# 5_-_Power.net
KiCad netlist of a schematic drawn in Altium Designer
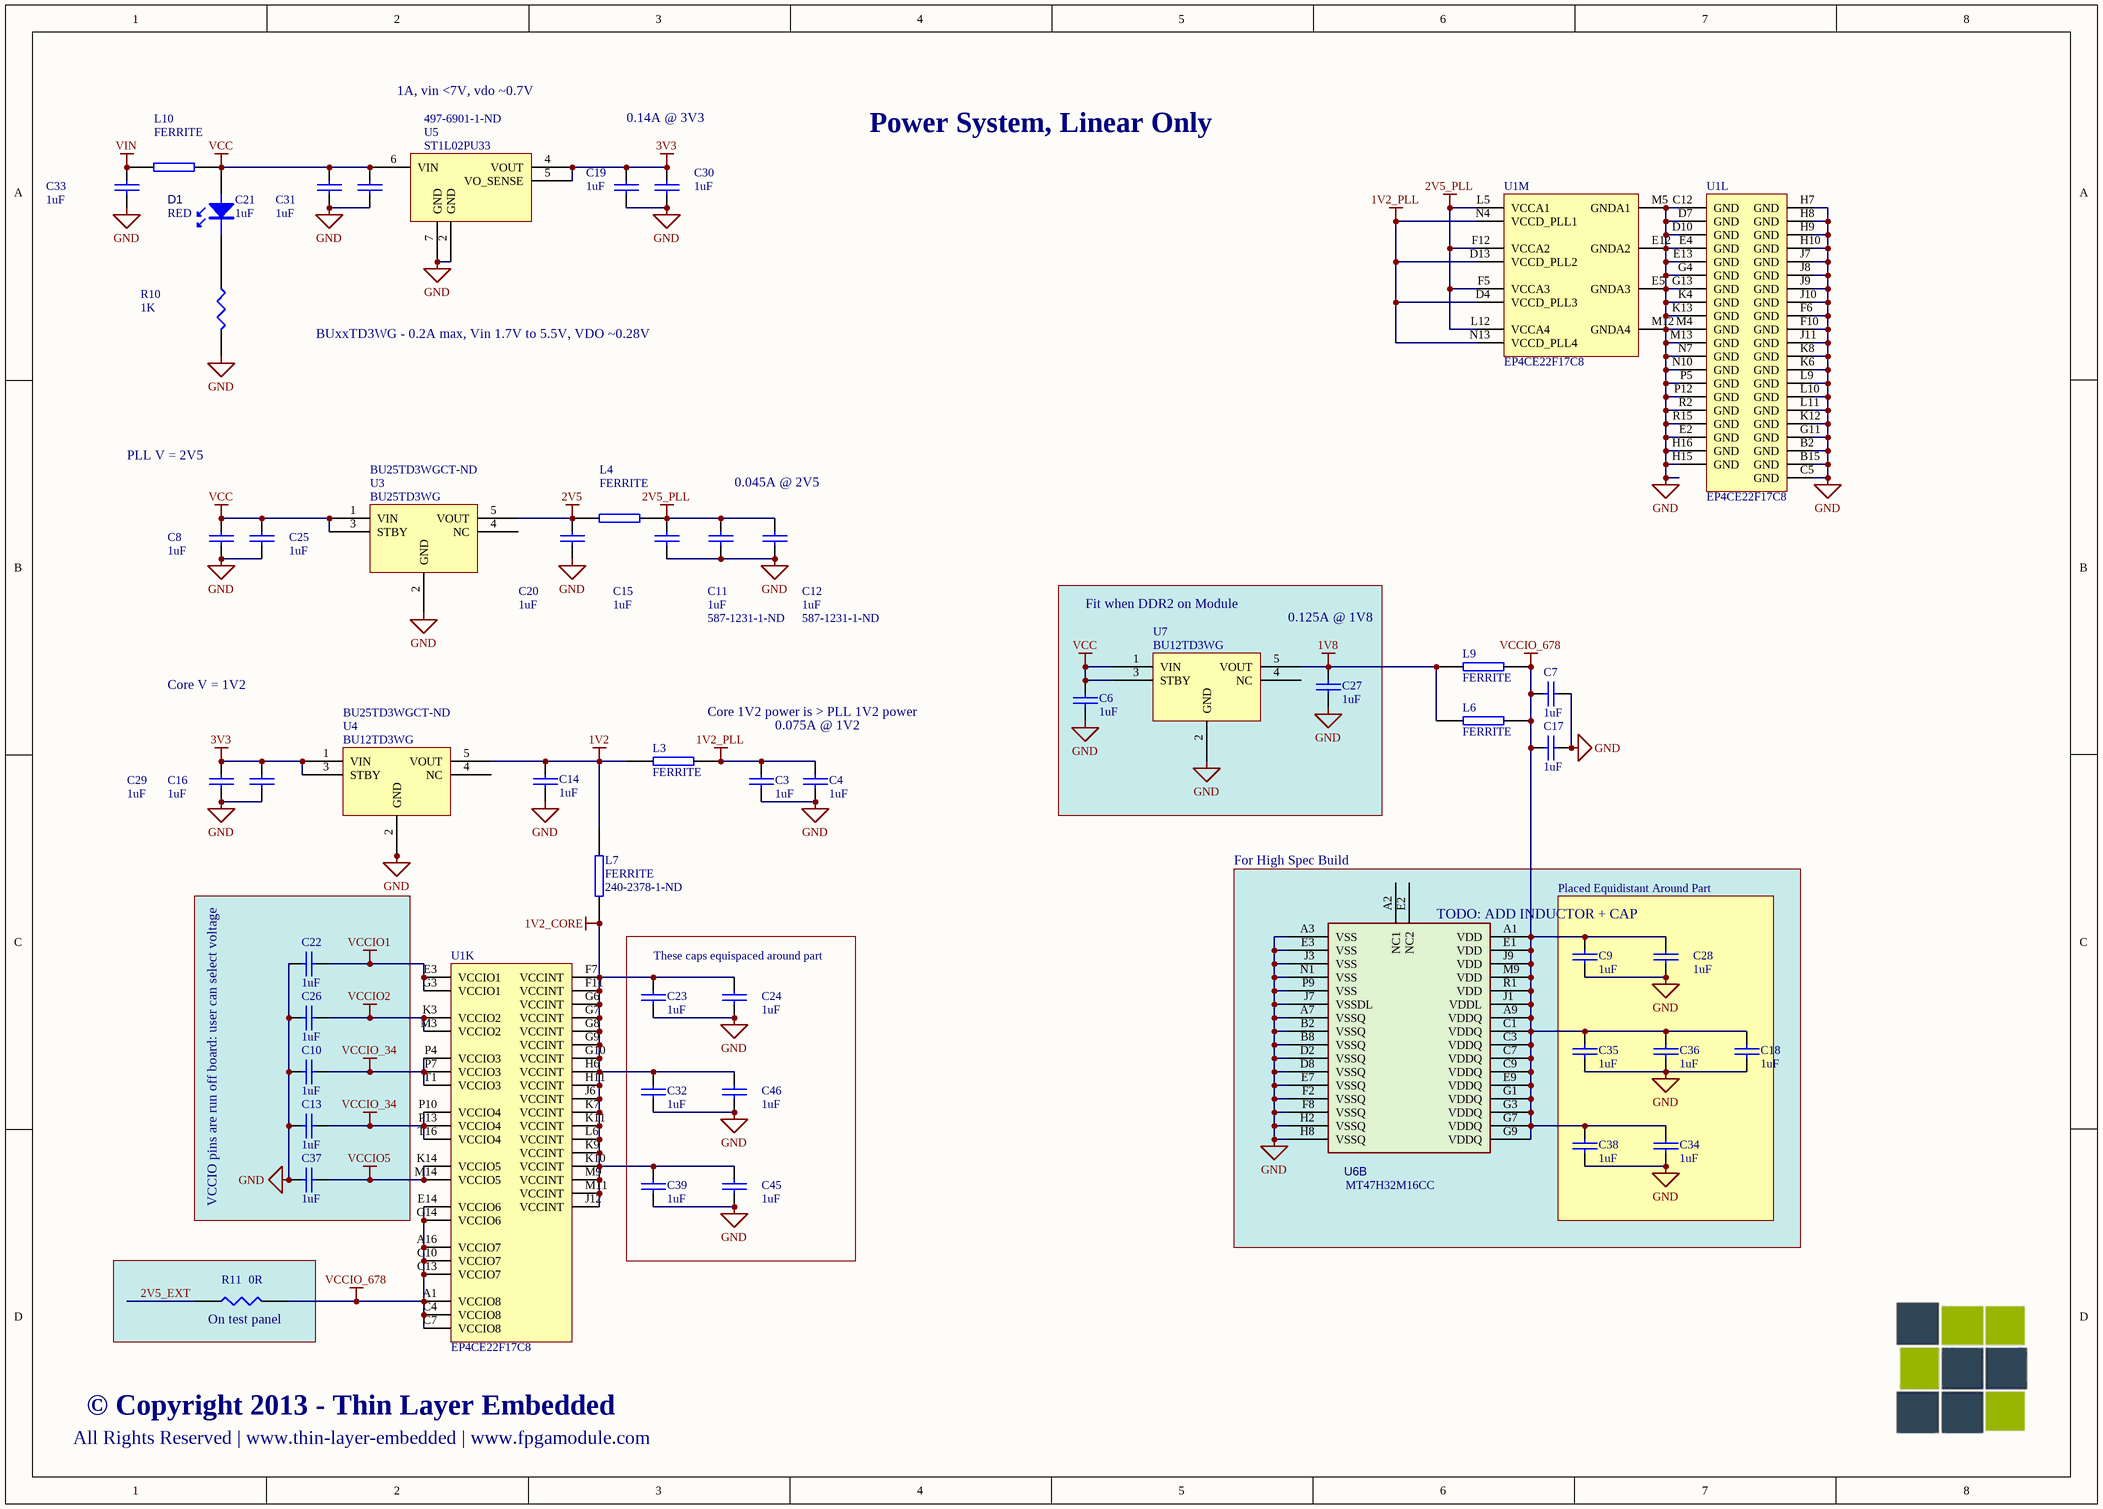
[diagram p0: 5 - Power.SchDoc]

(export (version "E")
  (design (tool "Eeschema 10.0.6"))
  (components
    (comp (ref "C3")
      (value "1uF")
      (footprint "0402_HD")
      (description "Capacitor")
      (libsource (lib "*") (part "CAP"))
    )
    (comp (ref "C4")
      (value "1uF")
      (footprint "0402_HD")
      (description "Capacitor")
      (libsource (lib "*") (part "CAP"))
    )
    (comp (ref "C6")
      (value "1uF")
      (footprint "0402_HD")
      (description "Capacitor")
      (libsource (lib "*") (part "CAP"))
    )
    (comp (ref "C7")
      (value "1uF")
      (footprint "0402_HD")
      (description "Capacitor")
      (libsource (lib "*") (part "CAP"))
    )
    (comp (ref "C8")
      (value "1uF")
      (footprint "0402_HD")
      (description "Capacitor")
      (libsource (lib "*") (part "CAP"))
    )
    (comp (ref "C9")
      (value "1uF")
      (footprint "0402_HD")
      (description "Capacitor")
      (libsource (lib "*") (part "CAP"))
    )
    (comp (ref "C10")
      (value "1uF")
      (footprint "0402_HD")
      (description "Capacitor")
      (libsource (lib "*") (part "CAP"))
    )
    (comp (ref "C11")
      (value "1uF")
      (footprint "0402_HD")
      (description "Capacitor")
      (fields (field (name "SUPPLIER PART NUMBER 2") "587-1231-1-ND"))
      (libsource (lib "*") (part "CAP"))
    )
    (comp (ref "C12")
      (value "1uF")
      (footprint "0402_HD")
      (description "Capacitor")
      (fields (field (name "SUPPLIER PART NUMBER 2") "587-1231-1-ND"))
      (libsource (lib "*") (part "CAP"))
    )
    (comp (ref "C13")
      (value "1uF")
      (footprint "0402_HD")
      (description "Capacitor")
      (libsource (lib "*") (part "CAP"))
    )
    (comp (ref "C14")
      (value "1uF")
      (footprint "0402_HD")
      (description "Capacitor")
      (libsource (lib "*") (part "CAP"))
    )
    (comp (ref "C15")
      (value "1uF")
      (footprint "0402_HD")
      (description "Capacitor")
      (libsource (lib "*") (part "CAP"))
    )
    (comp (ref "C16")
      (value "1uF")
      (footprint "0402_HD")
      (description "Capacitor")
      (libsource (lib "*") (part "CAP"))
    )
    (comp (ref "C17")
      (value "1uF")
      (footprint "0402_HD")
      (description "Capacitor")
      (libsource (lib "*") (part "CAP"))
    )
    (comp (ref "C18")
      (value "1uF")
      (footprint "0402_HD")
      (description "Capacitor")
      (libsource (lib "*") (part "CAP"))
    )
    (comp (ref "C19")
      (value "1uF")
      (footprint "0402_HD")
      (description "Capacitor")
      (libsource (lib "*") (part "CAP"))
    )
    (comp (ref "C20")
      (value "1uF")
      (footprint "0402_HD")
      (description "Capacitor")
      (libsource (lib "") (part "CAP_1"))
    )
    (comp (ref "C21")
      (value "1uF")
      (footprint "0402_HD")
      (description "Capacitor")
      (libsource (lib "*") (part "CAP"))
    )
    (comp (ref "C22")
      (value "1uF")
      (footprint "0402_HD")
      (description "Capacitor")
      (libsource (lib "*") (part "CAP"))
    )
    (comp (ref "C23")
      (value "1uF")
      (footprint "0402_HD")
      (description "Capacitor")
      (libsource (lib "*") (part "CAP"))
    )
    (comp (ref "C24")
      (value "1uF")
      (footprint "0402_HD")
      (description "Capacitor")
      (libsource (lib "*") (part "CAP"))
    )
    (comp (ref "C25")
      (value "1uF")
      (footprint "0402_HD")
      (description "Capacitor")
      (libsource (lib "*") (part "CAP"))
    )
    (comp (ref "C26")
      (value "1uF")
      (footprint "0402_HD")
      (description "Capacitor")
      (libsource (lib "*") (part "CAP"))
    )
    (comp (ref "C27")
      (value "1uF")
      (footprint "0402_HD")
      (description "Capacitor")
      (libsource (lib "*") (part "CAP"))
    )
    (comp (ref "C28")
      (value "1uF")
      (footprint "0402_HD")
      (description "Capacitor")
      (libsource (lib "*") (part "CAP"))
    )
    (comp (ref "C29")
      (value "1uF")
      (footprint "0402_HD")
      (description "Capacitor")
      (libsource (lib "*") (part "CAP"))
    )
    (comp (ref "C30")
      (value "1uF")
      (footprint "0402_HD")
      (description "Capacitor")
      (libsource (lib "*") (part "CAP"))
    )
    (comp (ref "C31")
      (value "1uF")
      (footprint "0402_HD")
      (description "Capacitor")
      (libsource (lib "*") (part "CAP"))
    )
    (comp (ref "C32")
      (value "1uF")
      (footprint "0402_HD")
      (description "Capacitor")
      (libsource (lib "*") (part "CAP"))
    )
    (comp (ref "C33")
      (value "1uF")
      (footprint "0402_HD")
      (description "Capacitor")
      (libsource (lib "*") (part "CAP"))
    )
    (comp (ref "C34")
      (value "1uF")
      (footprint "0402_HD")
      (description "Capacitor")
      (libsource (lib "*") (part "CAP"))
    )
    (comp (ref "C35")
      (value "1uF")
      (footprint "0402_HD")
      (description "Capacitor")
      (libsource (lib "*") (part "CAP"))
    )
    (comp (ref "C36")
      (value "1uF")
      (footprint "0402_HD")
      (description "Capacitor")
      (libsource (lib "*") (part "CAP"))
    )
    (comp (ref "C37")
      (value "1uF")
      (footprint "0402_HD")
      (description "Capacitor")
      (libsource (lib "*") (part "CAP"))
    )
    (comp (ref "C38")
      (value "1uF")
      (footprint "0402_HD")
      (description "Capacitor")
      (libsource (lib "*") (part "CAP"))
    )
    (comp (ref "C39")
      (value "1uF")
      (footprint "0402_HD")
      (description "Capacitor")
      (libsource (lib "*") (part "CAP"))
    )
    (comp (ref "C45")
      (value "1uF")
      (footprint "0402_HD")
      (description "Capacitor")
      (libsource (lib "*") (part "CAP"))
    )
    (comp (ref "C46")
      (value "1uF")
      (footprint "0402_HD")
      (description "Capacitor")
      (libsource (lib "*") (part "CAP"))
    )
    (comp (ref "D1") (value "RED") (footprint "0402LED_HD") (libsource (lib "*") (part "LED")))
    (comp (ref "L3") (value "FERRITE") (footprint "0402_HD") (libsource (lib "*") (part "FERRITE")))
    (comp (ref "L4") (value "FERRITE") (footprint "0402_HD") (libsource (lib "*") (part "FERRITE")))
    (comp (ref "L6") (value "FERRITE") (footprint "0402_HD") (libsource (lib "*") (part "FERRITE")))
    (comp (ref "L7")
      (value "FERRITE")
      (footprint "0402_HD")
      (description "FERRITE 200MA 1000 OHM 0603 SMD")
      (fields
        (field (name "SUPPLIER PART NUMBER 1") "240-2378-1-ND")
        (field (name "MANUFACTURER") "Laird-Signal Integrity Products")
        (field (name "MANUFACTURER PART NUMBER") "HZ0603B102R-10")
      )
      (libsource (lib "*") (part "FERRITE"))
    )
    (comp (ref "L9") (value "FERRITE") (footprint "0402_HD") (libsource (lib "*") (part "FERRITE")))
    (comp (ref "L10") (value "FERRITE") (footprint "0805") (libsource (lib "*") (part "FERRITE")))
    (comp (ref "R10") (value "1K") (footprint "0402_HD") (libsource (lib "*") (part "RES1")))
    (comp (ref "R11")
      (value "0R")
      (footprint "0402_HD")
      (description "RES 24.9 OHM 1/16W 1% 0402 SMD")
      (fields
        (field (name "MANUFACTURER") "Yageo")
        (field (name "MANUFACTURER PART NUMBER") "RC0402FR-0724R9L")
      )
      (libsource (lib "*") (part "RES1"))
    )
    (comp (ref "U1")
      (value "EP4CE22F17C8")
      (footprint "FBGA256")
      (fields (field (name "PUBLISHER") "Altium Limited"))
      (libsource (lib "Altera Cyclone IV E") (part "EP4CE22F17C8"))
    )
    (comp (ref "U3")
      (value "BU25TD3WG")
      (footprint "SSOP5")
      (description "IC REG LDO 2.5V 0.2A 5SSOP")
      (fields
        (field (name "SUPPLIER PART NUMBER 1") "BU25TD3WGCT-ND")
        (field (name "MANUFACTURER") "Rohm Semiconductor")
        (field (name "MANUFACTURER PART NUMBER") "BU25TD3WG-TR")
      )
      (libsource (lib "OB_EP4CE15E22") (part "BU12TD3WG"))
    )
    (comp (ref "U4")
      (value "BU12TD3WG")
      (footprint "SSOP5")
      (description "IC REG LDO 2.5V 0.2A 5SSOP")
      (fields
        (field (name "SUPPLIER PART NUMBER 1") "BU25TD3WGCT-ND")
        (field (name "MANUFACTURER") "Rohm Semiconductor")
        (field (name "MANUFACTURER PART NUMBER") "BU25TD3WG-TR")
      )
      (libsource (lib "OB_EP4CE15E22") (part "BU12TD3WG"))
    )
    (comp (ref "U5")
      (value "ST1L02PU33")
      (footprint "DFN6")
      (description "IC VREG LDO 1A 3.3V DFN-6D")
      (fields
        (field (name "SUPPLIER PART NUMBER 1") "497-6901-1-ND")
        (field (name "MANUFACTURER") "STMicroelectronics")
        (field (name "MANUFACTURER PART NUMBER") "ST1L02PU33R")
      )
      (libsource (lib "OB_EP4CE15E22") (part "ST1L02PU33"))
    )
    (comp (ref "U6")
      (value "MT47H32M16CC")
      (footprint "DDR2_84_SPEC_HD")
      (description "IC DDR2 SDRAM 32M X 16 4 BANKS 333MHZ CAS LATENCY 5 FBGA PACKAGE 84 PINS 1.8V CORE 1.8V IO")
      (fields
        (field (name "MANUFACTURER PART NUM") "MT47H32M16CC-3:B")
        (field (name "MANUFACTURER") "Micron")
      )
      (libsource (lib "tea133-sch-2") (part "MT47H32M16CC"))
    )
    (comp (ref "U7")
      (value "BU12TD3WG")
      (footprint "SSOP5")
      (libsource (lib "OB_EP4CE15E22") (part "BU12TD3WG"))
    )
  )
  (nets
    (net (code "1") (name "/2V5_EXT") (class "Default")
      (node (ref "R11") (pin "2") (pinfunction "2_2") (pintype "passive"))
    )
    (net (code "2") (name "1V2") (class "Default")
      (node (ref "C14") (pin "1") (pinfunction "1_1") (pintype "passive"))
      (node (ref "L3") (pin "2") (pinfunction "2_2") (pintype "passive"))
      (node (ref "L7") (pin "1") (pinfunction "1_1") (pintype "passive"))
      (node (ref "U4") (pin "5") (pinfunction "VOUT_5") (pintype "passive"))
    )
    (net (code "3") (name "1V2_CORE") (class "Default")
      (node (ref "C23") (pin "1") (pinfunction "1_1") (pintype "passive"))
      (node (ref "C24") (pin "1") (pinfunction "1_1") (pintype "passive"))
      (node (ref "C32") (pin "1") (pinfunction "1_1") (pintype "passive"))
      (node (ref "C39") (pin "1") (pinfunction "1_1") (pintype "passive"))
      (node (ref "C45") (pin "1") (pinfunction "1_1") (pintype "passive"))
      (node (ref "C46") (pin "1") (pinfunction "1_1") (pintype "passive"))
      (node (ref "L7") (pin "2") (pinfunction "2_2") (pintype "passive"))
      (node (ref "U1") (pin "F11") (pinfunction "VCCINT_F11") (pintype "power_in"))
      (node (ref "U1") (pin "F7") (pinfunction "VCCINT_F7") (pintype "power_in"))
      (node (ref "U1") (pin "G10") (pinfunction "VCCINT_G10") (pintype "power_in"))
      (node (ref "U1") (pin "G6") (pinfunction "VCCINT_G6") (pintype "power_in"))
      (node (ref "U1") (pin "G7") (pinfunction "VCCINT_G7") (pintype "power_in"))
      (node (ref "U1") (pin "G8") (pinfunction "VCCINT_G8") (pintype "power_in"))
      (node (ref "U1") (pin "G9") (pinfunction "VCCINT_G9") (pintype "power_in"))
      (node (ref "U1") (pin "H11") (pinfunction "VCCINT_H11") (pintype "power_in"))
      (node (ref "U1") (pin "H6") (pinfunction "VCCINT_H6") (pintype "power_in"))
      (node (ref "U1") (pin "J12") (pinfunction "VCCINT_J12") (pintype "power_in"))
      (node (ref "U1") (pin "J6") (pinfunction "VCCINT_J6") (pintype "power_in"))
      (node (ref "U1") (pin "K10") (pinfunction "VCCINT_K10") (pintype "power_in"))
      (node (ref "U1") (pin "K11") (pinfunction "VCCINT_K11") (pintype "power_in"))
      (node (ref "U1") (pin "K7") (pinfunction "VCCINT_K7") (pintype "power_in"))
      (node (ref "U1") (pin "K9") (pinfunction "VCCINT_K9") (pintype "power_in"))
      (node (ref "U1") (pin "L6") (pinfunction "VCCINT_L6") (pintype "power_in"))
      (node (ref "U1") (pin "M11") (pinfunction "VCCINT_M11") (pintype "power_in"))
      (node (ref "U1") (pin "M9") (pinfunction "VCCINT_M9") (pintype "power_in"))
    )
    (net (code "4") (name "1V2_PLL") (class "Default")
      (node (ref "C3") (pin "1") (pinfunction "1_1") (pintype "passive"))
      (node (ref "C4") (pin "1") (pinfunction "1_1") (pintype "passive"))
      (node (ref "L3") (pin "1") (pinfunction "1_1") (pintype "passive"))
      (node (ref "U1") (pin "D13") (pinfunction "VCCD_PLL2_D13") (pintype "power_in"))
      (node (ref "U1") (pin "D4") (pinfunction "VCCD_PLL3_D4") (pintype "power_in"))
      (node (ref "U1") (pin "N13") (pinfunction "VCCD_PLL4_N13") (pintype "power_in"))
      (node (ref "U1") (pin "N4") (pinfunction "VCCD_PLL1_N4") (pintype "power_in"))
    )
    (net (code "5") (name "1V8") (class "Default")
      (node (ref "C27") (pin "1") (pinfunction "1_1") (pintype "passive"))
      (node (ref "L6") (pin "1") (pinfunction "1_1") (pintype "passive"))
      (node (ref "L9") (pin "1") (pinfunction "1_1") (pintype "passive"))
      (node (ref "U7") (pin "5") (pinfunction "VOUT_5") (pintype "passive"))
    )
    (net (code "6") (name "2V5") (class "Default")
      (node (ref "C20") (pin "2") (pinfunction "2_2") (pintype "passive"))
      (node (ref "L4") (pin "1") (pinfunction "1_1") (pintype "passive"))
      (node (ref "U3") (pin "5") (pinfunction "VOUT_5") (pintype "passive"))
    )
    (net (code "7") (name "2V5_PLL") (class "Default")
      (node (ref "C11") (pin "1") (pinfunction "1_1") (pintype "passive"))
      (node (ref "C12") (pin "1") (pinfunction "1_1") (pintype "passive"))
      (node (ref "C15") (pin "1") (pinfunction "1_1") (pintype "passive"))
      (node (ref "L4") (pin "2") (pinfunction "2_2") (pintype "passive"))
      (node (ref "U1") (pin "F12") (pinfunction "VCCA2_F12") (pintype "power_in"))
      (node (ref "U1") (pin "F5") (pinfunction "VCCA3_F5") (pintype "power_in"))
      (node (ref "U1") (pin "L12") (pinfunction "VCCA4_L12") (pintype "power_in"))
      (node (ref "U1") (pin "L5") (pinfunction "VCCA1_L5") (pintype "power_in"))
    )
    (net (code "8") (name "3V3") (class "Default")
      (node (ref "C16") (pin "1") (pinfunction "1_1") (pintype "passive"))
      (node (ref "C19") (pin "1") (pinfunction "1_1") (pintype "passive"))
      (node (ref "C29") (pin "1") (pinfunction "1_1") (pintype "passive"))
      (node (ref "C30") (pin "1") (pinfunction "1_1") (pintype "passive"))
      (node (ref "U4") (pin "1") (pinfunction "VIN_1") (pintype "passive"))
      (node (ref "U4") (pin "3") (pinfunction "STBY_3") (pintype "passive"))
      (node (ref "U5") (pin "4") (pinfunction "VOUT_4") (pintype "passive"))
      (node (ref "U5") (pin "5") (pinfunction "VO_SENSE_5") (pintype "passive"))
    )
    (net (code "9") (name "GND") (class "Default")
      (node (ref "C10") (pin "1") (pinfunction "1_1") (pintype "passive"))
      (node (ref "C11") (pin "2") (pinfunction "2_2") (pintype "passive"))
      (node (ref "C12") (pin "2") (pinfunction "2_2") (pintype "passive"))
      (node (ref "C13") (pin "1") (pinfunction "1_1") (pintype "passive"))
      (node (ref "C14") (pin "2") (pinfunction "2_2") (pintype "passive"))
      (node (ref "C15") (pin "2") (pinfunction "2_2") (pintype "passive"))
      (node (ref "C16") (pin "2") (pinfunction "2_2") (pintype "passive"))
      (node (ref "C17") (pin "2") (pinfunction "2_2") (pintype "passive"))
      (node (ref "C18") (pin "2") (pinfunction "2_2") (pintype "passive"))
      (node (ref "C19") (pin "2") (pinfunction "2_2") (pintype "passive"))
      (node (ref "C20") (pin "1") (pinfunction "1_1") (pintype "passive"))
      (node (ref "C21") (pin "2") (pinfunction "2_2") (pintype "passive"))
      (node (ref "C22") (pin "1") (pinfunction "1_1") (pintype "passive"))
      (node (ref "C23") (pin "2") (pinfunction "2_2") (pintype "passive"))
      (node (ref "C24") (pin "2") (pinfunction "2_2") (pintype "passive"))
      (node (ref "C25") (pin "2") (pinfunction "2_2") (pintype "passive"))
      (node (ref "C26") (pin "1") (pinfunction "1_1") (pintype "passive"))
      (node (ref "C27") (pin "2") (pinfunction "2_2") (pintype "passive"))
      (node (ref "C28") (pin "2") (pinfunction "2_2") (pintype "passive"))
      (node (ref "C29") (pin "2") (pinfunction "2_2") (pintype "passive"))
      (node (ref "C3") (pin "2") (pinfunction "2_2") (pintype "passive"))
      (node (ref "C30") (pin "2") (pinfunction "2_2") (pintype "passive"))
      (node (ref "C31") (pin "2") (pinfunction "2_2") (pintype "passive"))
      (node (ref "C32") (pin "2") (pinfunction "2_2") (pintype "passive"))
      (node (ref "C33") (pin "1") (pinfunction "1_1") (pintype "passive"))
      (node (ref "C34") (pin "2") (pinfunction "2_2") (pintype "passive"))
      (node (ref "C35") (pin "2") (pinfunction "2_2") (pintype "passive"))
      (node (ref "C36") (pin "2") (pinfunction "2_2") (pintype "passive"))
      (node (ref "C37") (pin "1") (pinfunction "1_1") (pintype "passive"))
      (node (ref "C38") (pin "2") (pinfunction "2_2") (pintype "passive"))
      (node (ref "C39") (pin "2") (pinfunction "2_2") (pintype "passive"))
      (node (ref "C4") (pin "2") (pinfunction "2_2") (pintype "passive"))
      (node (ref "C45") (pin "2") (pinfunction "2_2") (pintype "passive"))
      (node (ref "C46") (pin "2") (pinfunction "2_2") (pintype "passive"))
      (node (ref "C6") (pin "2") (pinfunction "2_2") (pintype "passive"))
      (node (ref "C7") (pin "2") (pinfunction "2_2") (pintype "passive"))
      (node (ref "C8") (pin "2") (pinfunction "2_2") (pintype "passive"))
      (node (ref "C9") (pin "2") (pinfunction "2_2") (pintype "passive"))
      (node (ref "R10") (pin "1") (pinfunction "1_1") (pintype "passive"))
      (node (ref "U1") (pin "B15") (pinfunction "GND_B15") (pintype "power_in"))
      (node (ref "U1") (pin "B2") (pinfunction "GND_B2") (pintype "power_in"))
      (node (ref "U1") (pin "C12") (pinfunction "GND_C12") (pintype "power_in"))
      (node (ref "U1") (pin "C5") (pinfunction "GND_C5") (pintype "power_in"))
      (node (ref "U1") (pin "D10") (pinfunction "GND_D10") (pintype "power_in"))
      (node (ref "U1") (pin "D7") (pinfunction "GND_D7") (pintype "power_in"))
      (node (ref "U1") (pin "E12") (pinfunction "GNDA2_E12") (pintype "power_in"))
      (node (ref "U1") (pin "E13") (pinfunction "GND_E13") (pintype "power_in"))
      (node (ref "U1") (pin "E2") (pinfunction "GND_E2") (pintype "power_in"))
      (node (ref "U1") (pin "E4") (pinfunction "GND_E4") (pintype "power_in"))
      (node (ref "U1") (pin "E5") (pinfunction "GNDA3_E5") (pintype "power_in"))
      (node (ref "U1") (pin "F10") (pinfunction "GND_F10") (pintype "power_in"))
      (node (ref "U1") (pin "F6") (pinfunction "GND_F6") (pintype "power_in"))
      (node (ref "U1") (pin "G11") (pinfunction "GND_G11") (pintype "power_in"))
      (node (ref "U1") (pin "G13") (pinfunction "GND_G13") (pintype "power_in"))
      (node (ref "U1") (pin "G4") (pinfunction "GND_G4") (pintype "power_in"))
      (node (ref "U1") (pin "H10") (pinfunction "GND_H10") (pintype "power_in"))
      (node (ref "U1") (pin "H15") (pinfunction "GND_H15") (pintype "power_in"))
      (node (ref "U1") (pin "H16") (pinfunction "GND_H16") (pintype "power_in"))
      (node (ref "U1") (pin "H7") (pinfunction "GND_H7") (pintype "power_in"))
      (node (ref "U1") (pin "H8") (pinfunction "GND_H8") (pintype "power_in"))
      (node (ref "U1") (pin "H9") (pinfunction "GND_H9") (pintype "power_in"))
      (node (ref "U1") (pin "J10") (pinfunction "GND_J10") (pintype "power_in"))
      (node (ref "U1") (pin "J11") (pinfunction "GND_J11") (pintype "power_in"))
      (node (ref "U1") (pin "J7") (pinfunction "GND_J7") (pintype "power_in"))
      (node (ref "U1") (pin "J8") (pinfunction "GND_J8") (pintype "power_in"))
      (node (ref "U1") (pin "J9") (pinfunction "GND_J9") (pintype "power_in"))
      (node (ref "U1") (pin "K12") (pinfunction "GND_K12") (pintype "power_in"))
      (node (ref "U1") (pin "K13") (pinfunction "GND_K13") (pintype "power_in"))
      (node (ref "U1") (pin "K4") (pinfunction "GND_K4") (pintype "power_in"))
      (node (ref "U1") (pin "K6") (pinfunction "GND_K6") (pintype "power_in"))
      (node (ref "U1") (pin "K8") (pinfunction "GND_K8") (pintype "power_in"))
      (node (ref "U1") (pin "L10") (pinfunction "GND_L10") (pintype "power_in"))
      (node (ref "U1") (pin "L11") (pinfunction "GND_L11") (pintype "power_in"))
      (node (ref "U1") (pin "L9") (pinfunction "GND_L9") (pintype "power_in"))
      (node (ref "U1") (pin "M12") (pinfunction "GNDA4_M12") (pintype "power_in"))
      (node (ref "U1") (pin "M13") (pinfunction "GND_M13") (pintype "power_in"))
      (node (ref "U1") (pin "M4") (pinfunction "GND_M4") (pintype "power_in"))
      (node (ref "U1") (pin "M5") (pinfunction "GNDA1_M5") (pintype "power_in"))
      (node (ref "U1") (pin "N10") (pinfunction "GND_N10") (pintype "power_in"))
      (node (ref "U1") (pin "N7") (pinfunction "GND_N7") (pintype "power_in"))
      (node (ref "U1") (pin "P12") (pinfunction "GND_P12") (pintype "power_in"))
      (node (ref "U1") (pin "P5") (pinfunction "GND_P5") (pintype "power_in"))
      (node (ref "U1") (pin "R15") (pinfunction "GND_R15") (pintype "power_in"))
      (node (ref "U1") (pin "R2") (pinfunction "GND_R2") (pintype "power_in"))
      (node (ref "U3") (pin "2") (pinfunction "GND_2") (pintype "passive"))
      (node (ref "U4") (pin "2") (pinfunction "GND_2") (pintype "passive"))
      (node (ref "U5") (pin "2") (pinfunction "GND_2") (pintype "passive"))
      (node (ref "U5") (pin "7") (pinfunction "GND_7") (pintype "passive"))
      (node (ref "U6") (pin "A3") (pinfunction "VSS_A3") (pintype "power_in"))
      (node (ref "U6") (pin "A7") (pinfunction "VSSQ_A7") (pintype "power_in"))
      (node (ref "U6") (pin "B2") (pinfunction "VSSQ_B2") (pintype "power_in"))
      (node (ref "U6") (pin "B8") (pinfunction "VSSQ_B8") (pintype "power_in"))
      (node (ref "U6") (pin "D2") (pinfunction "VSSQ_D2") (pintype "power_in"))
      (node (ref "U6") (pin "D8") (pinfunction "VSSQ_D8") (pintype "power_in"))
      (node (ref "U6") (pin "E3") (pinfunction "VSS_E3") (pintype "power_in"))
      (node (ref "U6") (pin "E7") (pinfunction "VSSQ_E7") (pintype "power_in"))
      (node (ref "U6") (pin "F2") (pinfunction "VSSQ_F2") (pintype "power_in"))
      (node (ref "U6") (pin "F8") (pinfunction "VSSQ_F8") (pintype "power_in"))
      (node (ref "U6") (pin "H2") (pinfunction "VSSQ_H2") (pintype "power_in"))
      (node (ref "U6") (pin "H8") (pinfunction "VSSQ_H8") (pintype "power_in"))
      (node (ref "U6") (pin "J3") (pinfunction "VSS_J3") (pintype "power_in"))
      (node (ref "U6") (pin "J7") (pinfunction "VSSDL_J7") (pintype "power_in"))
      (node (ref "U6") (pin "N1") (pinfunction "VSS_N1") (pintype "power_in"))
      (node (ref "U6") (pin "P9") (pinfunction "VSS_P9") (pintype "power_in"))
      (node (ref "U7") (pin "2") (pinfunction "GND_2") (pintype "passive"))
    )
    (net (code "10") (name "Net-(D1-2)") (class "Default")
      (node (ref "D1") (pin "K") (pinfunction "2_K") (pintype "passive"))
      (node (ref "R10") (pin "2") (pinfunction "2_2") (pintype "passive"))
    )
    (net (code "11") (name "VCC") (class "Default")
      (node (ref "C21") (pin "1") (pinfunction "1_1") (pintype "passive"))
      (node (ref "C25") (pin "1") (pinfunction "1_1") (pintype "passive"))
      (node (ref "C31") (pin "1") (pinfunction "1_1") (pintype "passive"))
      (node (ref "C6") (pin "1") (pinfunction "1_1") (pintype "passive"))
      (node (ref "C8") (pin "1") (pinfunction "1_1") (pintype "passive"))
      (node (ref "D1") (pin "A") (pinfunction "1_A") (pintype "passive"))
      (node (ref "L10") (pin "2") (pinfunction "2_2") (pintype "passive"))
      (node (ref "U3") (pin "1") (pinfunction "VIN_1") (pintype "passive"))
      (node (ref "U3") (pin "3") (pinfunction "STBY_3") (pintype "passive"))
      (node (ref "U5") (pin "6") (pinfunction "VIN_6") (pintype "passive"))
      (node (ref "U7") (pin "1") (pinfunction "VIN_1") (pintype "passive"))
      (node (ref "U7") (pin "3") (pinfunction "STBY_3") (pintype "passive"))
    )
    (net (code "12") (name "VCCIO1") (class "Default")
      (node (ref "C22") (pin "2") (pinfunction "2_2") (pintype "passive"))
      (node (ref "U1") (pin "E3") (pinfunction "VCCIO1_E3") (pintype "power_in"))
      (node (ref "U1") (pin "G3") (pinfunction "VCCIO1_G3") (pintype "power_in"))
    )
    (net (code "13") (name "VCCIO2") (class "Default")
      (node (ref "C26") (pin "2") (pinfunction "2_2") (pintype "passive"))
      (node (ref "U1") (pin "K3") (pinfunction "VCCIO2_K3") (pintype "power_in"))
      (node (ref "U1") (pin "M3") (pinfunction "VCCIO2_M3") (pintype "power_in"))
    )
    (net (code "14") (name "VCCIO5") (class "Default")
      (node (ref "C37") (pin "2") (pinfunction "2_2") (pintype "passive"))
      (node (ref "U1") (pin "K14") (pinfunction "VCCIO5_K14") (pintype "power_in"))
      (node (ref "U1") (pin "M14") (pinfunction "VCCIO5_M14") (pintype "power_in"))
    )
    (net (code "15") (name "VCCIO_34") (class "Default")
      (node (ref "C10") (pin "2") (pinfunction "2_2") (pintype "passive"))
      (node (ref "C13") (pin "2") (pinfunction "2_2") (pintype "passive"))
      (node (ref "U1") (pin "P10") (pinfunction "VCCIO4_P10") (pintype "power_in"))
      (node (ref "U1") (pin "P13") (pinfunction "VCCIO4_P13") (pintype "power_in"))
      (node (ref "U1") (pin "P4") (pinfunction "VCCIO3_P4") (pintype "power_in"))
      (node (ref "U1") (pin "P7") (pinfunction "VCCIO3_P7") (pintype "power_in"))
      (node (ref "U1") (pin "T1") (pinfunction "VCCIO3_T1") (pintype "power_in"))
      (node (ref "U1") (pin "T16") (pinfunction "VCCIO4_T16") (pintype "power_in"))
    )
    (net (code "16") (name "VCCIO_678") (class "Default")
      (node (ref "C17") (pin "1") (pinfunction "1_1") (pintype "passive"))
      (node (ref "C18") (pin "1") (pinfunction "1_1") (pintype "passive"))
      (node (ref "C28") (pin "1") (pinfunction "1_1") (pintype "passive"))
      (node (ref "C34") (pin "1") (pinfunction "1_1") (pintype "passive"))
      (node (ref "C35") (pin "1") (pinfunction "1_1") (pintype "passive"))
      (node (ref "C36") (pin "1") (pinfunction "1_1") (pintype "passive"))
      (node (ref "C38") (pin "1") (pinfunction "1_1") (pintype "passive"))
      (node (ref "C7") (pin "1") (pinfunction "1_1") (pintype "passive"))
      (node (ref "C9") (pin "1") (pinfunction "1_1") (pintype "passive"))
      (node (ref "L6") (pin "2") (pinfunction "2_2") (pintype "passive"))
      (node (ref "L9") (pin "2") (pinfunction "2_2") (pintype "passive"))
      (node (ref "R11") (pin "1") (pinfunction "1_1") (pintype "passive"))
      (node (ref "U1") (pin "A1") (pinfunction "VCCIO8_A1") (pintype "power_in"))
      (node (ref "U1") (pin "A16") (pinfunction "VCCIO7_A16") (pintype "power_in"))
      (node (ref "U1") (pin "C10") (pinfunction "VCCIO7_C10") (pintype "power_in"))
      (node (ref "U1") (pin "C13") (pinfunction "VCCIO7_C13") (pintype "power_in"))
      (node (ref "U1") (pin "C4") (pinfunction "VCCIO8_C4") (pintype "power_in"))
      (node (ref "U1") (pin "C7") (pinfunction "VCCIO8_C7") (pintype "power_in"))
      (node (ref "U1") (pin "E14") (pinfunction "VCCIO6_E14") (pintype "power_in"))
      (node (ref "U1") (pin "G14") (pinfunction "VCCIO6_G14") (pintype "power_in"))
      (node (ref "U6") (pin "A1") (pinfunction "VDD_A1") (pintype "power_in"))
      (node (ref "U6") (pin "A9") (pinfunction "VDDQ_A9") (pintype "power_in"))
      (node (ref "U6") (pin "C1") (pinfunction "VDDQ_C1") (pintype "power_in"))
      (node (ref "U6") (pin "C3") (pinfunction "VDDQ_C3") (pintype "power_in"))
      (node (ref "U6") (pin "C7") (pinfunction "VDDQ_C7") (pintype "power_in"))
      (node (ref "U6") (pin "C9") (pinfunction "VDDQ_C9") (pintype "power_in"))
      (node (ref "U6") (pin "E1") (pinfunction "VDD_E1") (pintype "power_in"))
      (node (ref "U6") (pin "E9") (pinfunction "VDDQ_E9") (pintype "power_in"))
      (node (ref "U6") (pin "G1") (pinfunction "VDDQ_G1") (pintype "power_in"))
      (node (ref "U6") (pin "G3") (pinfunction "VDDQ_G3") (pintype "power_in"))
      (node (ref "U6") (pin "G7") (pinfunction "VDDQ_G7") (pintype "power_in"))
      (node (ref "U6") (pin "G9") (pinfunction "VDDQ_G9") (pintype "power_in"))
      (node (ref "U6") (pin "J1") (pinfunction "VDDL_J1") (pintype "power_in"))
      (node (ref "U6") (pin "J9") (pinfunction "VDD_J9") (pintype "power_in"))
      (node (ref "U6") (pin "M9") (pinfunction "VDD_M9") (pintype "power_in"))
      (node (ref "U6") (pin "R1") (pinfunction "VDD_R1") (pintype "power_in"))
    )
    (net (code "17") (name "VIN") (class "Default")
      (node (ref "C33") (pin "2") (pinfunction "2_2") (pintype "passive"))
      (node (ref "L10") (pin "1") (pinfunction "1_1") (pintype "passive"))
    )
    (net (code "18") (name "unconnected-(U3-NC-Pad4)") (class "Default")
      (node (ref "U3") (pin "4") (pinfunction "NC_4") (pintype "passive"))
    )
    (net (code "19") (name "unconnected-(U4-NC-Pad4)") (class "Default")
      (node (ref "U4") (pin "4") (pinfunction "NC_4") (pintype "passive"))
    )
    (net (code "20") (name "unconnected-(U6B-NC1-PadA2)") (class "Default")
      (node (ref "U6") (pin "A2") (pinfunction "NC1_A2") (pintype "passive"))
    )
    (net (code "21") (name "unconnected-(U6B-NC2-PadE2)") (class "Default")
      (node (ref "U6") (pin "E2") (pinfunction "NC2_E2") (pintype "passive"))
    )
    (net (code "22") (name "unconnected-(U7-NC-Pad4)") (class "Default")
      (node (ref "U7") (pin "4") (pinfunction "NC_4") (pintype "passive"))
    )
  )
)
